# PLCfilters.net
KiCad netlist of a schematic drawn in Altium Designer
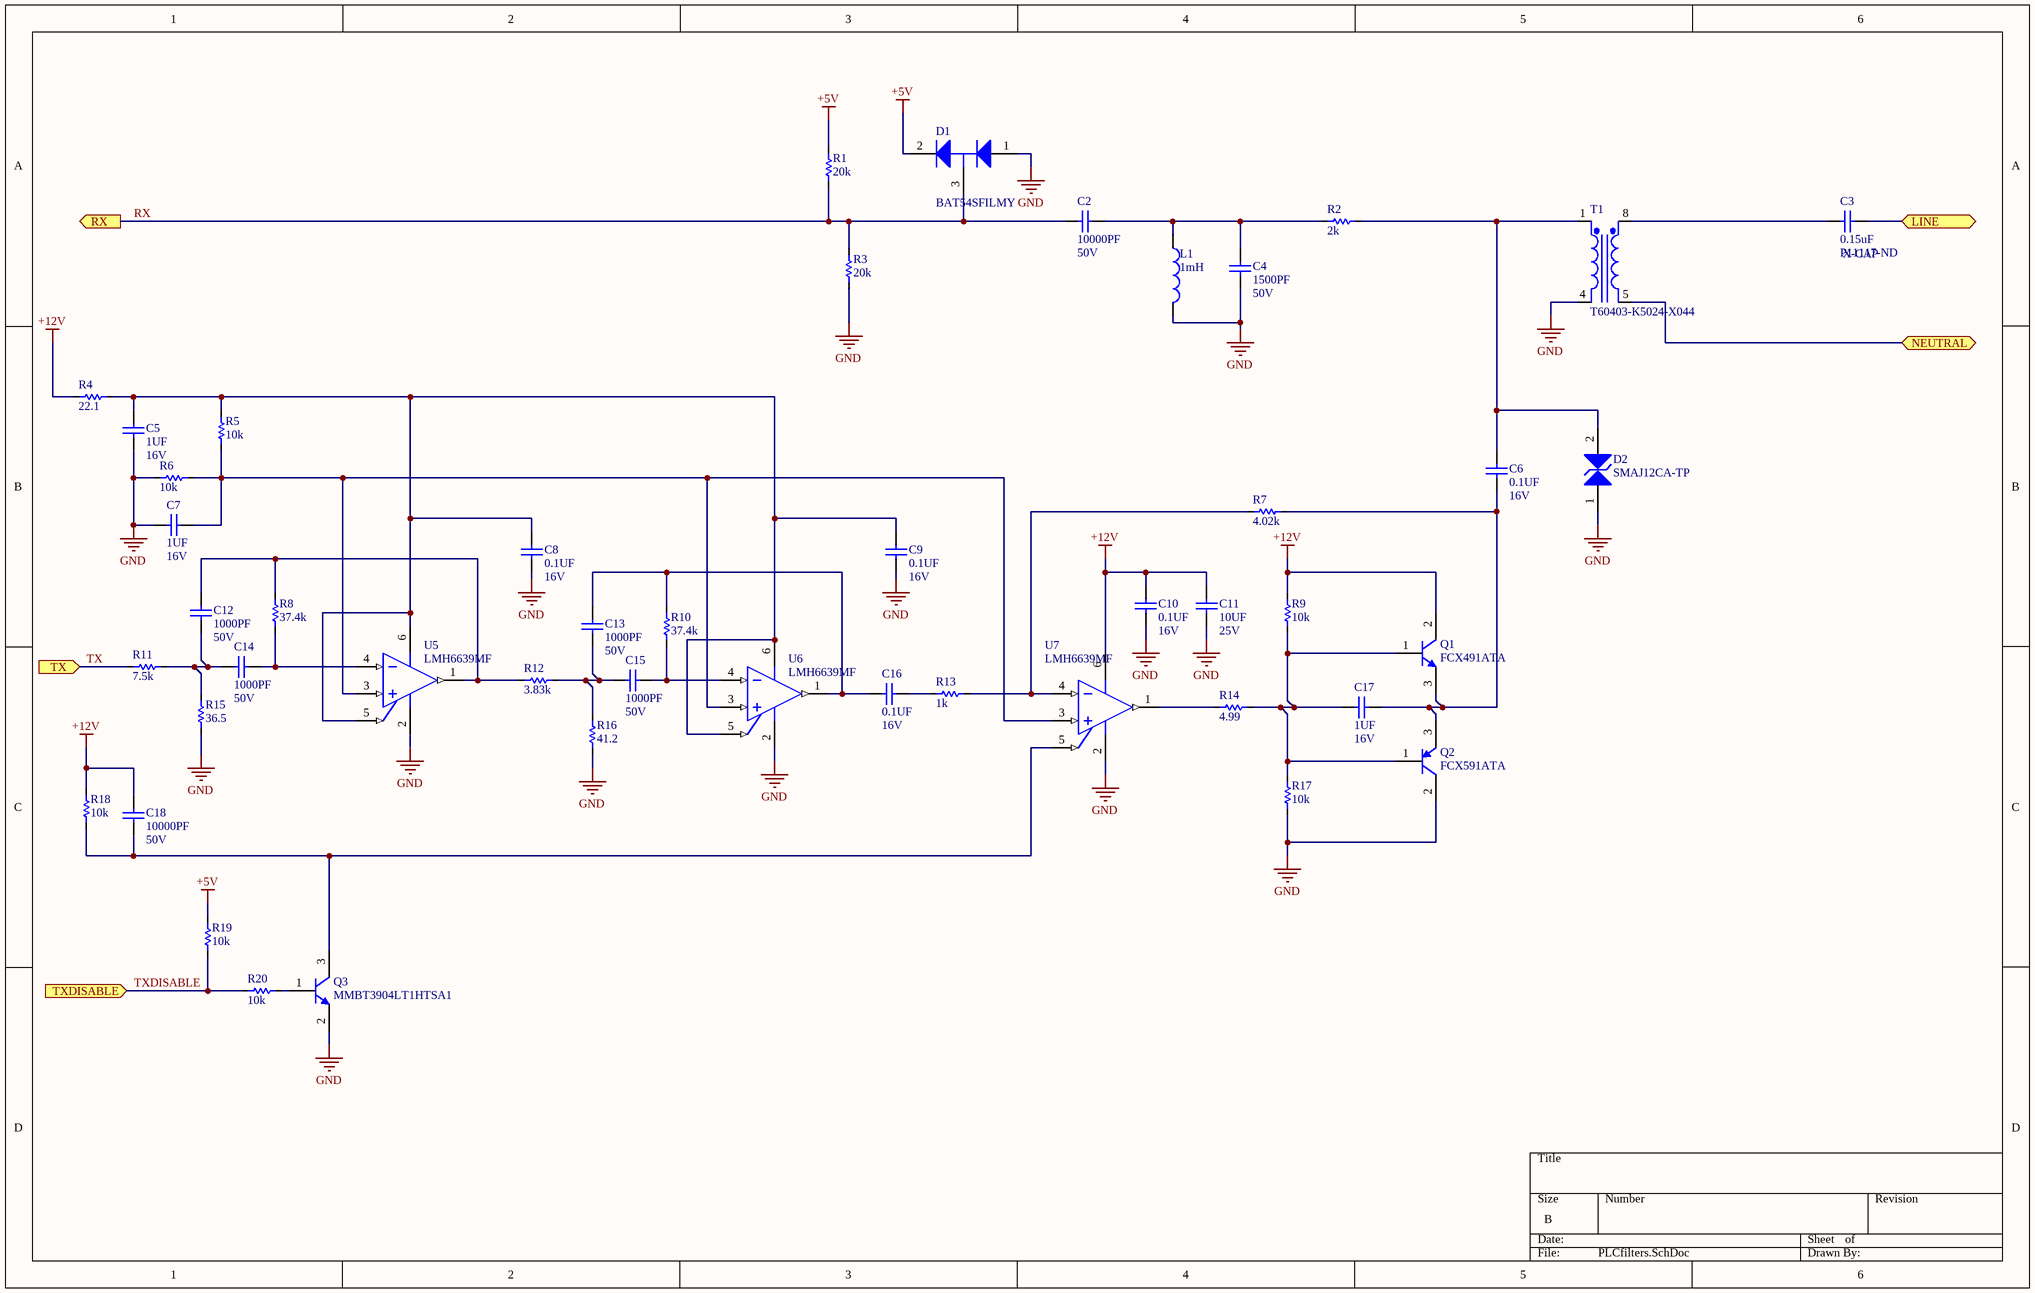
[diagram p0: PLCfilters.SchDoc]

(export (version "E")
  (design (tool "Eeschema 10.0.6"))
  (components
    (comp (ref "C2")
      (value "GRM188R71H103KA01D")
      (footprint "CAPC1608X08N")
      (description "CAP CER 10000PF 50V X7R 0603")
      (fields
        (field (name "MANUFACTURER") "Murata Electronics North America")
        (field (name "CAPACITANCE") "10000PF")
        (field (name "VOLTAGE - RATED") "50V")
      )
      (libsource (lib "IntelligentJunctionBox") (part "GRM188R71H103KA01D"))
    )
    (comp (ref "C3")
      (value "0.15uF")
      (footprint "ECQ-U3A154MG")
      (description "CAP FILM 0.15UF 20% 300VAC RAD")
      (fields
        (field (name "MANUFACTURER PART NUMBER") "ECQ-U3A154MG")
        (field (name "MANUFACTURER") "Murata")
        (field (name "SUPPLIER PART NUMBER 1") "P11117-ND")
      )
      (libsource (lib "IntelligentJunctionBox") (part "ECQ-U3A154MG"))
    )
    (comp (ref "C4")
      (value "GRM188R71H152KA01D")
      (footprint "CAPC1608X08N")
      (description "CAP CER 1500PF 50V X7R 0603")
      (fields
        (field (name "MANUFACTURER") "Murata Electronics North America")
        (field (name "CAPACITANCE") "1500PF")
        (field (name "VOLTAGE - RATED") "50V")
      )
      (libsource (lib "IntelligentJunctionBox") (part "GRM188R71H152KA01D"))
    )
    (comp (ref "C5")
      (value "GRM188R71C105KE15D")
      (footprint "CAPC1608X08N")
      (description "CAP CER 1UF 16V X7R 0603")
      (fields
        (field (name "MANUFACTURER") "Murata Electronics North America")
        (field (name "CAPACITANCE") "1UF")
        (field (name "VOLTAGE - RATED") "16V")
      )
      (libsource (lib "IntelligentJunctionBox") (part "GRM188R71C105KE15D"))
    )
    (comp (ref "C6")
      (value "GRM188R71C104KA01D")
      (footprint "CAPC1608X08N")
      (description "CAP CER 0.1UF 16V X7R 0603")
      (fields
        (field (name "MANUFACTURER") "Murata Electronics North America")
        (field (name "CAPACITANCE") "0.1UF")
        (field (name "VOLTAGE - RATED") "16V")
      )
      (libsource (lib "IntelligentJunctionBox") (part "GRM188R71C104KA01D"))
    )
    (comp (ref "C7")
      (value "GRM188R71C105KE15D")
      (footprint "CAPC1608X08N")
      (description "CAP CER 1UF 16V X7R 0603")
      (fields
        (field (name "MANUFACTURER") "Murata Electronics North America")
        (field (name "CAPACITANCE") "1UF")
        (field (name "VOLTAGE - RATED") "16V")
      )
      (libsource (lib "IntelligentJunctionBox") (part "GRM188R71C105KE15D"))
    )
    (comp (ref "C8")
      (value "GRM188R71C104KA01D")
      (footprint "CAPC1608X08N")
      (description "CAP CER 0.1UF 16V X7R 0603")
      (fields
        (field (name "MANUFACTURER") "Murata Electronics North America")
        (field (name "CAPACITANCE") "0.1UF")
        (field (name "VOLTAGE - RATED") "16V")
      )
      (libsource (lib "IntelligentJunctionBox") (part "GRM188R71C104KA01D"))
    )
    (comp (ref "C9")
      (value "GRM188R71C104KA01D")
      (footprint "CAPC1608X08N")
      (description "CAP CER 0.1UF 16V X7R 0603")
      (fields
        (field (name "MANUFACTURER") "Murata Electronics North America")
        (field (name "CAPACITANCE") "0.1UF")
        (field (name "VOLTAGE - RATED") "16V")
      )
      (libsource (lib "IntelligentJunctionBox") (part "GRM188R71C104KA01D"))
    )
    (comp (ref "C10")
      (value "GRM188R71C104KA01D")
      (footprint "CAPC1608X08N")
      (description "CAP CER 0.1UF 16V X7R 0603")
      (fields
        (field (name "MANUFACTURER") "Murata Electronics North America")
        (field (name "CAPACITANCE") "0.1UF")
        (field (name "VOLTAGE - RATED") "16V")
      )
      (libsource (lib "IntelligentJunctionBox") (part "GRM188R71C104KA01D"))
    )
    (comp (ref "C11")
      (value "GRM319R61E106KA12D")
      (footprint "CAPC3216X16N")
      (description "CAP CER 10UF 25V X5R 1206")
      (fields
        (field (name "MANUFACTURER") "Murata Electronics North America")
        (field (name "CAPACITANCE") "10UF")
        (field (name "VOLTAGE - RATED") "25V")
      )
      (libsource (lib "IntelligentJunctionBox") (part "GRM319R61E106KA12D"))
    )
    (comp (ref "C12")
      (value "GRM1885C1H102JA01D")
      (footprint "CAPC1608X08N")
      (description "CAP CER 1000PF 50V C0G/NP0 0603")
      (fields
        (field (name "MANUFACTURER") "Murata Electronics North America")
        (field (name "CAPACITANCE") "1000PF")
        (field (name "VOLTAGE - RATED") "50V")
      )
      (libsource (lib "IntelligentJunctionBox") (part "GRM1885C1H102JA01D"))
    )
    (comp (ref "C13")
      (value "GRM1885C1H102JA01D")
      (footprint "CAPC1608X08N")
      (description "CAP CER 1000PF 50V C0G/NP0 0603")
      (fields
        (field (name "MANUFACTURER") "Murata Electronics North America")
        (field (name "CAPACITANCE") "1000PF")
        (field (name "VOLTAGE - RATED") "50V")
      )
      (libsource (lib "IntelligentJunctionBox") (part "GRM1885C1H102JA01D"))
    )
    (comp (ref "C14")
      (value "GRM1885C1H102JA01D")
      (footprint "CAPC1608X08N")
      (description "CAP CER 1000PF 50V C0G/NP0 0603")
      (fields
        (field (name "MANUFACTURER") "Murata Electronics North America")
        (field (name "CAPACITANCE") "1000PF")
        (field (name "VOLTAGE - RATED") "50V")
      )
      (libsource (lib "IntelligentJunctionBox") (part "GRM1885C1H102JA01D"))
    )
    (comp (ref "C15")
      (value "GRM1885C1H102JA01D")
      (footprint "CAPC1608X08N")
      (description "CAP CER 1000PF 50V C0G/NP0 0603")
      (fields
        (field (name "MANUFACTURER") "Murata Electronics North America")
        (field (name "CAPACITANCE") "1000PF")
        (field (name "VOLTAGE - RATED") "50V")
      )
      (libsource (lib "IntelligentJunctionBox") (part "GRM1885C1H102JA01D"))
    )
    (comp (ref "C16")
      (value "GRM188R71C104KA01D")
      (footprint "CAPC1608X08N")
      (description "CAP CER 0.1UF 16V X7R 0603")
      (fields
        (field (name "MANUFACTURER") "Murata Electronics North America")
        (field (name "CAPACITANCE") "0.1UF")
        (field (name "VOLTAGE - RATED") "16V")
      )
      (libsource (lib "IntelligentJunctionBox") (part "GRM188R71C104KA01D"))
    )
    (comp (ref "C17")
      (value "GRM188R71C105KE15D")
      (footprint "CAPC1608X08N")
      (description "CAP CER 1UF 16V X7R 0603")
      (fields
        (field (name "MANUFACTURER") "Murata Electronics North America")
        (field (name "CAPACITANCE") "1UF")
        (field (name "VOLTAGE - RATED") "16V")
      )
      (libsource (lib "IntelligentJunctionBox") (part "GRM188R71C105KE15D"))
    )
    (comp (ref "C18")
      (value "GRM188R71H103KA01D")
      (footprint "CAPC1608X08N")
      (description "CAP CER 10000PF 50V X7R 0603")
      (fields
        (field (name "MANUFACTURER") "Murata Electronics North America")
        (field (name "CAPACITANCE") "10000PF")
        (field (name "VOLTAGE - RATED") "50V")
      )
      (libsource (lib "IntelligentJunctionBox") (part "GRM188R71H103KA01D"))
    )
    (comp (ref "D1")
      (value "BAT54SFILMY")
      (footprint "SOT95P240X110-3N")
      (description "DIODE ARRAY SCHOTTKY 40V SOT23-3")
      (fields (field (name "MANUFACTURER") "STMicroelectronics"))
      (libsource (lib "IntelligentJunctionBox") (part "BAT54SFILMY"))
    )
    (comp (ref "D2")
      (value "SMAJ12CA-TP")
      (footprint "DO-214AC")
      (description "TVS DIODE 12VWM 19.9VC SMA")
      (fields (field (name "MANUFACTURER") "Micro Commercial Co"))
      (libsource (lib "IntelligentJunctionBox") (part "SMAJ12CA-TP"))
    )
    (comp (ref "L1")
      (value "1mH")
      (footprint "INDC2518X20N")
      (description "FIXED IND 1MH 75MA 31.2 OHM SMD")
      (fields
        (field (name "MANUFACTURER") "Taiyo Yuden")
        (field (name "MANUFACTURER PART NUMBER") "CB2518T102K")
      )
      (libsource (lib "IntelligentJunctionBox") (part "CB2518T102K"))
    )
    (comp (ref "Q1")
      (value "FCX491ATA")
      (footprint "SOT89-150P409X160-3N")
      (description "TRANS NPN 40V 1A SOT-89")
      (fields (field (name "MANUFACTURER") "Diodes Incorporated"))
      (libsource (lib "IntelligentJunctionBox") (part "FCX491ATA"))
    )
    (comp (ref "Q2")
      (value "FCX591ATA")
      (footprint "SOT89-150P409X160-3N")
      (description "TRANS PNP 40V 1A SOT-89")
      (fields (field (name "MANUFACTURER") "Diodes Incorporated"))
      (libsource (lib "IntelligentJunctionBox") (part "FCX591ATA"))
    )
    (comp (ref "Q3")
      (value "MMBT3904LT1HTSA1")
      (footprint "SOT95P240X110-3N")
      (description "TRANS NPN 40V 0.2A SOT-23")
      (fields (field (name "MANUFACTURER") "Infineon Technologies"))
      (libsource (lib "IntelligentJunctionBox") (part "MMBT3904LT1HTSA1"))
    )
    (comp (ref "R1")
      (value "RC0603FR-0720KL")
      (footprint "RESC1608X06N")
      (description "RES SMD 20K OHM 1% 1/10W 0603")
      (fields (field (name "MANUFACTURER") "Yageo") (field (name "RESISTANCE") "20k"))
      (libsource (lib "IntelligentJunctionBox") (part "RC0603FR-0720KL"))
    )
    (comp (ref "R2")
      (value "RC0603FR-072KL")
      (footprint "RESC1608X06N")
      (description "RES SMD 2K OHM 1% 1/10W 0603")
      (fields (field (name "MANUFACTURER") "Yageo") (field (name "RESISTANCE") "2k"))
      (libsource (lib "IntelligentJunctionBox") (part "RC0603FR-072KL"))
    )
    (comp (ref "R3")
      (value "RC0603FR-0720KL")
      (footprint "RESC1608X06N")
      (description "RES SMD 20K OHM 1% 1/10W 0603")
      (fields (field (name "MANUFACTURER") "Yageo") (field (name "RESISTANCE") "20k"))
      (libsource (lib "IntelligentJunctionBox") (part "RC0603FR-0720KL"))
    )
    (comp (ref "R4")
      (value "RC0603FR-0722R1L")
      (footprint "RESC1608X06N")
      (description "RES SMD 22.1 OHM 1% 1/10W 0603")
      (fields (field (name "MANUFACTURER") "Yageo") (field (name "RESISTANCE") "22.1"))
      (libsource (lib "IntelligentJunctionBox") (part "RC0603FR-0722R1L"))
    )
    (comp (ref "R5")
      (value "RC0603FR-0710KL")
      (footprint "RESC1608X06N")
      (description "RES SMD 10K OHM 1% 1/10W 0603")
      (fields (field (name "MANUFACTURER") "Yageo") (field (name "RESISTANCE") "10k"))
      (libsource (lib "IntelligentJunctionBox") (part "RC0603FR-0710KL"))
    )
    (comp (ref "R6")
      (value "RC0603FR-0710KL")
      (footprint "RESC1608X06N")
      (description "RES SMD 10K OHM 1% 1/10W 0603")
      (fields (field (name "MANUFACTURER") "Yageo") (field (name "RESISTANCE") "10k"))
      (libsource (lib "IntelligentJunctionBox") (part "RC0603FR-0710KL"))
    )
    (comp (ref "R7")
      (value "RC0603FR-074K02L")
      (footprint "RESC1608X06N")
      (description "RES SMD 4.02K OHM 1% 1/10W 0603")
      (fields (field (name "MANUFACTURER") "Yageo") (field (name "RESISTANCE") "4.02k"))
      (libsource (lib "IntelligentJunctionBox") (part "RC0603FR-074K02L"))
    )
    (comp (ref "R8")
      (value "RC0603FR-0737K4L")
      (footprint "RESC1608X06N")
      (description "RES SMD 37.4K OHM 1% 1/10W 0603")
      (fields (field (name "MANUFACTURER") "Yageo") (field (name "RESISTANCE") "37.4k"))
      (libsource (lib "IntelligentJunctionBox") (part "RC0603FR-0737K4L"))
    )
    (comp (ref "R9")
      (value "RC0603FR-0710KL")
      (footprint "RESC1608X06N")
      (description "RES SMD 10K OHM 1% 1/10W 0603")
      (fields (field (name "MANUFACTURER") "Yageo") (field (name "RESISTANCE") "10k"))
      (libsource (lib "IntelligentJunctionBox") (part "RC0603FR-0710KL"))
    )
    (comp (ref "R10")
      (value "RC0603FR-0737K4L")
      (footprint "RESC1608X06N")
      (description "RES SMD 37.4K OHM 1% 1/10W 0603")
      (fields (field (name "MANUFACTURER") "Yageo") (field (name "RESISTANCE") "37.4k"))
      (libsource (lib "IntelligentJunctionBox") (part "RC0603FR-0737K4L"))
    )
    (comp (ref "R11")
      (value "AC0603FR-077K5L")
      (footprint "RESC1608X06N")
      (description "RES SMD 7.5K OHM 1% 1/10W 0603")
      (fields (field (name "MANUFACTURER") "Yageo") (field (name "RESISTANCE") "7.5k"))
      (libsource (lib "IntelligentJunctionBox") (part "AC0603FR-077K5L"))
    )
    (comp (ref "R12")
      (value "RC0603FR-073K83L")
      (footprint "RESC1608X06N")
      (description "RES SMD 3.83K OHM 1% 1/10W 0603")
      (fields (field (name "MANUFACTURER") "Yageo") (field (name "RESISTANCE") "3.83k"))
      (libsource (lib "IntelligentJunctionBox") (part "RC0603FR-073K83L"))
    )
    (comp (ref "R13")
      (value "RC0603FR-071KL")
      (footprint "RESC1608X06N")
      (description "RES SMD 1K OHM 1% 1/10W 0603")
      (fields
        (field (name "MANUFACTURER") "Yageo")
        (field (name "MANUFACTURER PART NUMBER") "RC0603FR-0710K7L")
        (field (name "RESISTANCE") "1k")
      )
      (libsource (lib "IntelligentJunctionBox") (part "RC0603FR-071KL"))
    )
    (comp (ref "R14")
      (value "RC0603FR-074R99L")
      (footprint "RESC1608X06N")
      (description "RES SMD 4.99 OHM 1% 1/10W 0603")
      (fields (field (name "MANUFACTURER") "Yageo") (field (name "RESISTANCE") "4.99"))
      (libsource (lib "IntelligentJunctionBox") (part "RC0603FR-074R99L"))
    )
    (comp (ref "R15")
      (value "RC0603FR-0736R5L")
      (footprint "RESC1608X06N")
      (description "RES SMD 36.5 OHM 1% 1/10W 0603")
      (fields (field (name "MANUFACTURER") "Yageo") (field (name "RESISTANCE") "36.5"))
      (libsource (lib "IntelligentJunctionBox") (part "RC0603FR-0736R5L"))
    )
    (comp (ref "R16")
      (value "RC0603FR-0741R2L")
      (footprint "RESC1608X06N")
      (description "RES SMD 41.2 OHM 1% 1/10W 0603")
      (fields (field (name "MANUFACTURER") "Yageo") (field (name "RESISTANCE") "41.2"))
      (libsource (lib "IntelligentJunctionBox") (part "RC0603FR-0741R2L"))
    )
    (comp (ref "R17")
      (value "RC0603FR-0710KL")
      (footprint "RESC1608X06N")
      (description "RES SMD 10K OHM 1% 1/10W 0603")
      (fields (field (name "MANUFACTURER") "Yageo") (field (name "RESISTANCE") "10k"))
      (libsource (lib "IntelligentJunctionBox") (part "RC0603FR-0710KL"))
    )
    (comp (ref "R18")
      (value "RC0603FR-0710KL")
      (footprint "RESC1608X06N")
      (description "RES SMD 10K OHM 1% 1/10W 0603")
      (fields (field (name "MANUFACTURER") "Yageo") (field (name "RESISTANCE") "10k"))
      (libsource (lib "IntelligentJunctionBox") (part "RC0603FR-0710KL"))
    )
    (comp (ref "R19")
      (value "RC0603FR-0710KL")
      (footprint "RESC1608X06N")
      (description "RES SMD 10K OHM 1% 1/10W 0603")
      (fields (field (name "MANUFACTURER") "Yageo") (field (name "RESISTANCE") "10k"))
      (libsource (lib "IntelligentJunctionBox") (part "RC0603FR-0710KL"))
    )
    (comp (ref "R20")
      (value "RC0603FR-0710KL")
      (footprint "RESC1608X06N")
      (description "RES SMD 10K OHM 1% 1/10W 0603")
      (fields (field (name "MANUFACTURER") "Yageo") (field (name "RESISTANCE") "10k"))
      (libsource (lib "IntelligentJunctionBox") (part "RC0603FR-0710KL"))
    )
    (comp (ref "T1")
      (value "T60403-K5024-X044")
      (footprint "T60403-K5024-X044")
      (description "Audio Transformers / Signal Transformers PLC Transf PTH SMD 1.4mH 1:1")
      (fields (field (name "MANUFACTURER") "Vacuumschmelze"))
      (libsource (lib "IntelligentJunctionBox") (part "T60403-K5024-X044"))
    )
    (comp (ref "U5")
      (value "LMH6639MF")
      (footprint "SOT95P280X145-6N")
      (description "IC OPAMP VFB 90MHZ RRO SOT23-6")
      (fields (field (name "MANUFACTURER") "Texas Instruments"))
      (libsource (lib "IntelligentJunctionBox") (part "LMH6639MF"))
    )
    (comp (ref "U6")
      (value "LMH6639MF")
      (footprint "SOT95P280X145-6N")
      (description "IC OPAMP VFB 90MHZ RRO SOT23-6")
      (fields (field (name "MANUFACTURER") "Texas Instruments"))
      (libsource (lib "IntelligentJunctionBox") (part "LMH6639MF"))
    )
    (comp (ref "U7")
      (value "LMH6639MF")
      (footprint "SOT95P280X145-6N")
      (description "IC OPAMP VFB 90MHZ RRO SOT23-6")
      (fields (field (name "MANUFACTURER") "Texas Instruments"))
      (libsource (lib "IntelligentJunctionBox") (part "LMH6639MF"))
    )
  )
  (nets
    (net (code "1") (name "+5V") (class "Default")
      (node (ref "D1") (pin "2") (pinfunction "K_2") (pintype "passive"))
      (node (ref "R1") (pin "2") (pinfunction "2_2") (pintype "passive"))
      (node (ref "R19") (pin "2") (pinfunction "2_2") (pintype "passive"))
    )
    (net (code "2") (name "+12V") (class "Default")
      (node (ref "C10") (pin "2") (pinfunction "2_2") (pintype "passive"))
      (node (ref "C11") (pin "2") (pinfunction "2_2") (pintype "passive"))
      (node (ref "C18") (pin "2") (pinfunction "2_2") (pintype "passive"))
      (node (ref "Q1") (pin "2") (pinfunction "C_2") (pintype "passive"))
      (node (ref "R18") (pin "2") (pinfunction "2_2") (pintype "passive"))
      (node (ref "R4") (pin "1") (pinfunction "1_1") (pintype "passive"))
      (node (ref "R9") (pin "2") (pinfunction "2_2") (pintype "passive"))
      (node (ref "U7") (pin "6") (pinfunction "V+_6") (pintype "power_in"))
    )
    (net (code "3") (name "/LINE") (class "Default")
      (node (ref "C3") (pin "1") (pinfunction "1_1") (pintype "passive"))
    )
    (net (code "4") (name "/NEUTRAL") (class "Default")
      (node (ref "T1") (pin "5") (pinfunction "Sec-_5") (pintype "passive"))
    )
    (net (code "5") (name "/RX") (class "Default")
      (node (ref "C2") (pin "2") (pinfunction "2_2") (pintype "passive"))
      (node (ref "D1") (pin "3") (pinfunction "C_3") (pintype "passive"))
      (node (ref "R1") (pin "1") (pinfunction "1_1") (pintype "passive"))
      (node (ref "R3") (pin "2") (pinfunction "2_2") (pintype "passive"))
    )
    (net (code "6") (name "/TX") (class "Default")
      (node (ref "R11") (pin "1") (pinfunction "1_1") (pintype "passive"))
    )
    (net (code "7") (name "/TXDISABLE") (class "Default")
      (node (ref "R19") (pin "1") (pinfunction "1_1") (pintype "passive"))
      (node (ref "R20") (pin "2") (pinfunction "2_2") (pintype "passive"))
    )
    (net (code "8") (name "GND") (class "Default")
      (node (ref "C10") (pin "1") (pinfunction "1_1") (pintype "passive"))
      (node (ref "C11") (pin "1") (pinfunction "1_1") (pintype "passive"))
      (node (ref "C4") (pin "1") (pinfunction "1_1") (pintype "passive"))
      (node (ref "C5") (pin "1") (pinfunction "1_1") (pintype "passive"))
      (node (ref "C7") (pin "2") (pinfunction "2_2") (pintype "passive"))
      (node (ref "C8") (pin "1") (pinfunction "1_1") (pintype "passive"))
      (node (ref "C9") (pin "1") (pinfunction "1_1") (pintype "passive"))
      (node (ref "D1") (pin "1") (pinfunction "A_1") (pintype "passive"))
      (node (ref "D2") (pin "1") (pinfunction "A_1") (pintype "passive"))
      (node (ref "L1") (pin "2") (pinfunction "2_2") (pintype "passive"))
      (node (ref "Q2") (pin "2") (pinfunction "C_2") (pintype "passive"))
      (node (ref "Q3") (pin "2") (pinfunction "E_2") (pintype "passive"))
      (node (ref "R15") (pin "1") (pinfunction "1_1") (pintype "passive"))
      (node (ref "R16") (pin "1") (pinfunction "1_1") (pintype "passive"))
      (node (ref "R17") (pin "1") (pinfunction "1_1") (pintype "passive"))
      (node (ref "R3") (pin "1") (pinfunction "1_1") (pintype "passive"))
      (node (ref "R6") (pin "1") (pinfunction "1_1") (pintype "passive"))
      (node (ref "T1") (pin "4") (pinfunction "Pri-_4") (pintype "passive"))
      (node (ref "U5") (pin "2") (pinfunction "V-_2") (pintype "power_in"))
      (node (ref "U6") (pin "2") (pinfunction "V-_2") (pintype "power_in"))
      (node (ref "U7") (pin "2") (pinfunction "V-_2") (pintype "power_in"))
    )
    (net (code "9") (name "Net-(C2-Pad1)") (class "Default")
      (node (ref "C2") (pin "1") (pinfunction "1_1") (pintype "passive"))
      (node (ref "C4") (pin "2") (pinfunction "2_2") (pintype "passive"))
      (node (ref "L1") (pin "1") (pinfunction "1_1") (pintype "passive"))
      (node (ref "R2") (pin "1") (pinfunction "1_1") (pintype "passive"))
    )
    (net (code "10") (name "Net-(C12-Pad1)") (class "Default")
      (node (ref "C12") (pin "1") (pinfunction "1_1") (pintype "passive"))
      (node (ref "C14") (pin "1") (pinfunction "1_1") (pintype "passive"))
      (node (ref "R11") (pin "2") (pinfunction "2_2") (pintype "passive"))
      (node (ref "R15") (pin "2") (pinfunction "2_2") (pintype "passive"))
    )
    (net (code "11") (name "Net-(C13-Pad1)") (class "Default")
      (node (ref "C13") (pin "1") (pinfunction "1_1") (pintype "passive"))
      (node (ref "C15") (pin "1") (pinfunction "1_1") (pintype "passive"))
      (node (ref "R12") (pin "2") (pinfunction "2_2") (pintype "passive"))
      (node (ref "R16") (pin "2") (pinfunction "2_2") (pintype "passive"))
    )
    (net (code "12") (name "Net-(C16-Pad2)") (class "Default")
      (node (ref "C16") (pin "2") (pinfunction "2_2") (pintype "passive"))
      (node (ref "R13") (pin "1") (pinfunction "1_1") (pintype "passive"))
    )
    (net (code "13") (name "Net-(D2-K)") (class "Default")
      (node (ref "C6") (pin "2") (pinfunction "2_2") (pintype "passive"))
      (node (ref "D2") (pin "2") (pinfunction "K_2") (pintype "passive"))
      (node (ref "R2") (pin "2") (pinfunction "2_2") (pintype "passive"))
      (node (ref "T1") (pin "1") (pinfunction "Pri+_1") (pintype "passive"))
    )
    (net (code "14") (name "Net-(Q1-B)") (class "Default")
      (node (ref "C17") (pin "1") (pinfunction "1_1") (pintype "passive"))
      (node (ref "Q1") (pin "1") (pinfunction "B_1") (pintype "passive"))
      (node (ref "Q2") (pin "1") (pinfunction "B_1") (pintype "passive"))
      (node (ref "R14") (pin "2") (pinfunction "2_2") (pintype "passive"))
      (node (ref "R17") (pin "2") (pinfunction "2_2") (pintype "passive"))
      (node (ref "R9") (pin "1") (pinfunction "1_1") (pintype "passive"))
    )
    (net (code "15") (name "Net-(Q1-E)") (class "Default")
      (node (ref "C17") (pin "2") (pinfunction "2_2") (pintype "passive"))
      (node (ref "C6") (pin "1") (pinfunction "1_1") (pintype "passive"))
      (node (ref "Q1") (pin "3") (pinfunction "E_3") (pintype "passive"))
      (node (ref "Q2") (pin "3") (pinfunction "E_3") (pintype "passive"))
      (node (ref "R7") (pin "2") (pinfunction "2_2") (pintype "passive"))
    )
    (net (code "16") (name "Net-(Q3-B)") (class "Default")
      (node (ref "Q3") (pin "1") (pinfunction "B_1") (pintype "passive"))
      (node (ref "R20") (pin "1") (pinfunction "1_1") (pintype "passive"))
    )
    (net (code "17") (name "Net-(Q3-C)") (class "Default")
      (node (ref "C18") (pin "1") (pinfunction "1_1") (pintype "passive"))
      (node (ref "Q3") (pin "3") (pinfunction "C_3") (pintype "passive"))
      (node (ref "R18") (pin "1") (pinfunction "1_1") (pintype "passive"))
      (node (ref "U7") (pin "5") (pinfunction "nSD_5") (pintype "input"))
    )
    (net (code "18") (name "Net-(T1-Sec+)") (class "Default")
      (node (ref "C3") (pin "2") (pinfunction "2_2") (pintype "passive"))
      (node (ref "T1") (pin "8") (pinfunction "Sec+_8") (pintype "passive"))
    )
    (net (code "19") (name "Net-(U5-IN+)") (class "Default")
      (node (ref "C7") (pin "1") (pinfunction "1_1") (pintype "passive"))
      (node (ref "R5") (pin "1") (pinfunction "1_1") (pintype "passive"))
      (node (ref "R6") (pin "2") (pinfunction "2_2") (pintype "passive"))
      (node (ref "U5") (pin "3") (pinfunction "IN+_3") (pintype "input"))
      (node (ref "U6") (pin "3") (pinfunction "IN+_3") (pintype "input"))
      (node (ref "U7") (pin "3") (pinfunction "IN+_3") (pintype "input"))
    )
    (net (code "20") (name "Net-(U5-IN-)") (class "Default")
      (node (ref "C14") (pin "2") (pinfunction "2_2") (pintype "passive"))
      (node (ref "R8") (pin "1") (pinfunction "1_1") (pintype "passive"))
      (node (ref "U5") (pin "4") (pinfunction "IN-_4") (pintype "input"))
    )
    (net (code "21") (name "Net-(U5-OUT)") (class "Default")
      (node (ref "C12") (pin "2") (pinfunction "2_2") (pintype "passive"))
      (node (ref "R12") (pin "1") (pinfunction "1_1") (pintype "passive"))
      (node (ref "R8") (pin "2") (pinfunction "2_2") (pintype "passive"))
      (node (ref "U5") (pin "1") (pinfunction "OUT_1") (pintype "output"))
    )
    (net (code "22") (name "Net-(U5-V+)") (class "Default")
      (node (ref "C5") (pin "2") (pinfunction "2_2") (pintype "passive"))
      (node (ref "C8") (pin "2") (pinfunction "2_2") (pintype "passive"))
      (node (ref "C9") (pin "2") (pinfunction "2_2") (pintype "passive"))
      (node (ref "R4") (pin "2") (pinfunction "2_2") (pintype "passive"))
      (node (ref "R5") (pin "2") (pinfunction "2_2") (pintype "passive"))
      (node (ref "U5") (pin "5") (pinfunction "nSD_5") (pintype "input"))
      (node (ref "U5") (pin "6") (pinfunction "V+_6") (pintype "power_in"))
      (node (ref "U6") (pin "5") (pinfunction "nSD_5") (pintype "input"))
      (node (ref "U6") (pin "6") (pinfunction "V+_6") (pintype "power_in"))
    )
    (net (code "23") (name "Net-(U6-IN-)") (class "Default")
      (node (ref "C15") (pin "2") (pinfunction "2_2") (pintype "passive"))
      (node (ref "R10") (pin "1") (pinfunction "1_1") (pintype "passive"))
      (node (ref "U6") (pin "4") (pinfunction "IN-_4") (pintype "input"))
    )
    (net (code "24") (name "Net-(U6-OUT)") (class "Default")
      (node (ref "C13") (pin "2") (pinfunction "2_2") (pintype "passive"))
      (node (ref "C16") (pin "1") (pinfunction "1_1") (pintype "passive"))
      (node (ref "R10") (pin "2") (pinfunction "2_2") (pintype "passive"))
      (node (ref "U6") (pin "1") (pinfunction "OUT_1") (pintype "output"))
    )
    (net (code "25") (name "Net-(U7-IN-)") (class "Default")
      (node (ref "R13") (pin "2") (pinfunction "2_2") (pintype "passive"))
      (node (ref "R7") (pin "1") (pinfunction "1_1") (pintype "passive"))
      (node (ref "U7") (pin "4") (pinfunction "IN-_4") (pintype "input"))
    )
    (net (code "26") (name "Net-(U7-OUT)") (class "Default")
      (node (ref "R14") (pin "1") (pinfunction "1_1") (pintype "passive"))
      (node (ref "U7") (pin "1") (pinfunction "OUT_1") (pintype "output"))
    )
  )
)
